# LB_BIT_o5_DCMOTOR-v02_rev1.net
KiCad netlist of a schematic drawn in EAGLE
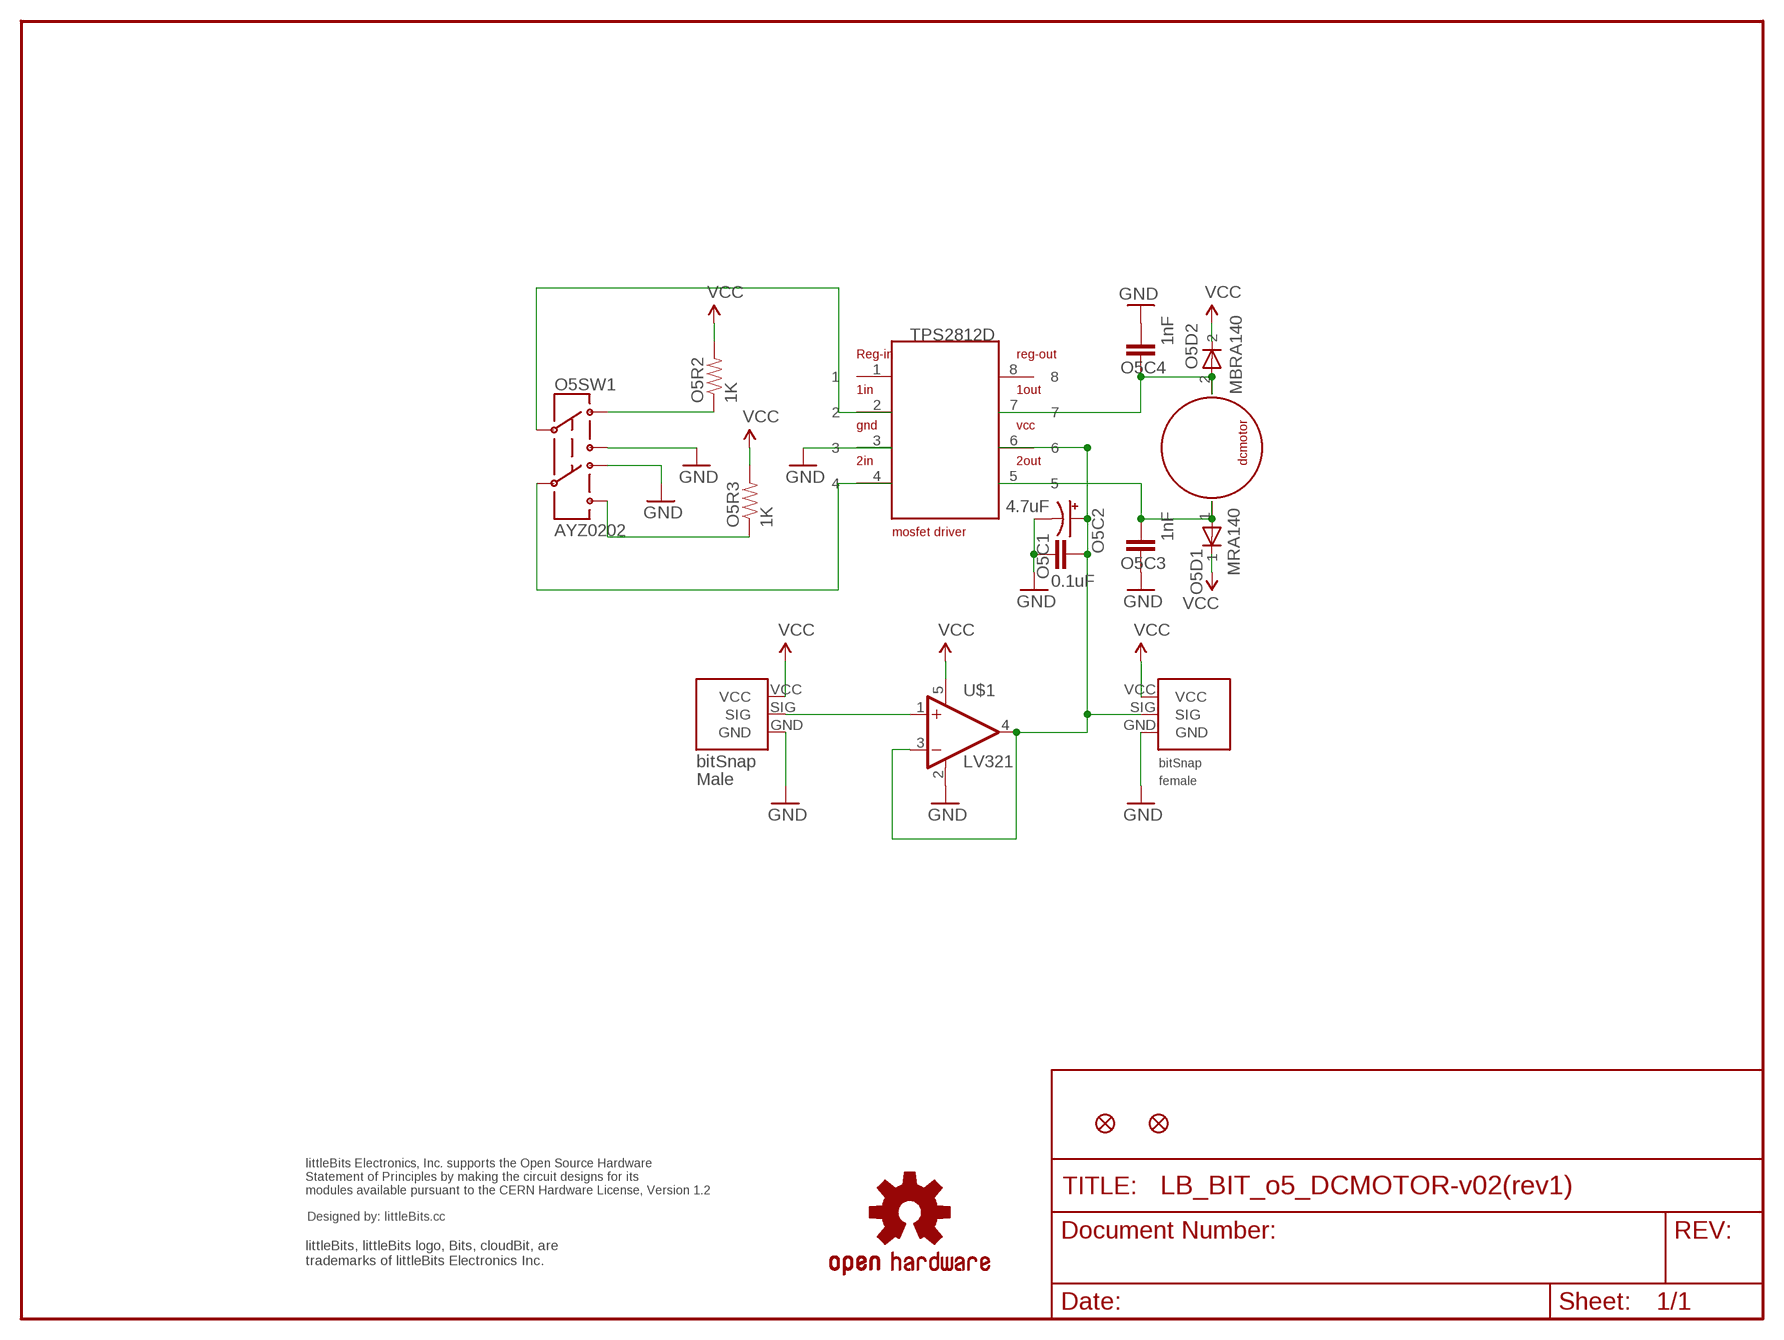
[diagram p0: schematic, sheet 1]

(export (version "E")
  (design (tool "Eeschema 10.0.6"))
  (components
    (comp (ref "JP1")
      (value "FIDUCIAL1X2")
      (footprint "eagle-import:FIDUCIAL-1X2")
      (libsource (lib "eagle-import") (part "FIDUCIAL1X2"))
    )
    (comp (ref "JP2")
      (value "FIDUCIAL1X2")
      (footprint "eagle-import:FIDUCIAL-1X2")
      (libsource (lib "eagle-import") (part "FIDUCIAL1X2"))
    )
    (comp (ref "O5BSF")
      (value "BITSNAP_FEMALE")
      (footprint "eagle-import:BITSNAP_FEMALE")
      (libsource (lib "eagle-import") (part "BITSNAP_FEMALE"))
    )
    (comp (ref "O5BSM")
      (value "BITSNAP_MALE")
      (footprint "eagle-import:BITSNAP_MALE")
      (libsource (lib "eagle-import") (part "BITSNAP_MALE"))
    )
    (comp (ref "O5C1")
      (value "0.1uF")
      (footprint "eagle-import:0603-CAP")
      (libsource (lib "eagle-import") (part "CAP0603-CAP"))
    )
    (comp (ref "O5C2")
      (value "4.7uF")
      (footprint "eagle-import:EIA3216")
      (libsource (lib "eagle-import") (part "CAP_POL1206"))
    )
    (comp (ref "O5C3")
      (value "1nF")
      (footprint "eagle-import:0603-CAP")
      (libsource (lib "eagle-import") (part "CAP0603-CAP"))
    )
    (comp (ref "O5C4")
      (value "1nF")
      (footprint "eagle-import:0603-CAP")
      (libsource (lib "eagle-import") (part "CAP0603-CAP"))
    )
    (comp (ref "O5D1")
      (value "MRA140")
      (footprint "eagle-import:SMA-DIODE")
      (libsource (lib "eagle-import") (part "DIODESMA"))
    )
    (comp (ref "O5D2")
      (value "MBRA140")
      (footprint "eagle-import:SMA-DIODE")
      (libsource (lib "eagle-import") (part "DIODESMA"))
    )
    (comp (ref "O5M1")
      (value "DCMOTOR")
      (footprint "eagle-import:MOTOR-DC")
      (libsource (lib "eagle-import") (part "DCMOTOR"))
    )
    (comp (ref "O5R2")
      (value "1K")
      (footprint "eagle-import:0603-RES")
      (libsource (lib "eagle-import") (part "RESISTOR0603-RES"))
    )
    (comp (ref "O5R3")
      (value "1K")
      (footprint "eagle-import:0603-RES")
      (libsource (lib "eagle-import") (part "RESISTOR0603-RES"))
    )
    (comp (ref "O5SW1")
      (value "AYZ0202")
      (footprint "eagle-import:AYZ0202")
      (libsource (lib "eagle-import") (part "AYZ0202"))
    )
    (comp (ref "O5U1")
      (value "TPS2812-SOIC8")
      (footprint "eagle-import:TPS2812")
      (libsource (lib "eagle-import") (part "TPS2812-SOIC8"))
    )
    (comp (ref "U$1")
      (value "LV321")
      (footprint "eagle-import:SC70-5")
      (libsource (lib "eagle-import") (part "LV321"))
    )
    (comp (ref "U$4")
      (value "OSHW-LOGOL")
      (footprint "eagle-import:OSHW-LOGO-L")
      (libsource (lib "eagle-import") (part "OSHW-LOGOL"))
    )
    (comp (ref "U$6")
      (value "OSHWCREDIT")
      (footprint "eagle-import:OSHWCREDIT")
      (libsource (lib "eagle-import") (part "OSHWCREDIT"))
    )
  )
  (nets
    (net (code "1") (name "GND") (class "Default")
      (node (ref "O5BSF") (pin "GND") (pinfunction "GND_GND") (pintype "bidirectional"))
      (node (ref "O5BSM") (pin "GND") (pinfunction "GND_GND") (pintype "bidirectional"))
      (node (ref "O5C1") (pin "1") (pinfunction "1_1") (pintype "passive"))
      (node (ref "O5C2") (pin "C") (pinfunction "-_C") (pintype "passive"))
      (node (ref "O5C3") (pin "1") (pinfunction "1_1") (pintype "passive"))
      (node (ref "O5C4") (pin "2") (pinfunction "2_2") (pintype "passive"))
      (node (ref "O5SW1") (pin "1") (pinfunction "3_1") (pintype "bidirectional"))
      (node (ref "O5SW1") (pin "6") (pinfunction "4_6") (pintype "bidirectional"))
      (node (ref "O5U1") (pin "3") (pinfunction "3_3") (pintype "bidirectional"))
      (node (ref "U$1") (pin "2") (pinfunction "V-_2") (pintype "power_in"))
    )
    (net (code "2") (name "Net-(O5C2-+)") (class "Default")
      (node (ref "O5BSF") (pin "SIG") (pinfunction "SIG_SIG") (pintype "bidirectional"))
      (node (ref "O5C1") (pin "2") (pinfunction "2_2") (pintype "passive"))
      (node (ref "O5C2") (pin "A") (pinfunction "+_A") (pintype "passive"))
      (node (ref "O5U1") (pin "6") (pinfunction "6_6") (pintype "bidirectional"))
      (node (ref "U$1") (pin "3") (pinfunction "-IN_3") (pintype "input"))
      (node (ref "U$1") (pin "4") (pinfunction "OUT_4") (pintype "output"))
    )
    (net (code "3") (name "Net-(O5C3-Pad2)") (class "Default")
      (node (ref "O5C3") (pin "2") (pinfunction "2_2") (pintype "passive"))
      (node (ref "O5D1") (pin "A") (pinfunction "A_A") (pintype "passive"))
      (node (ref "O5M1") (pin "1") (pinfunction "1_1") (pintype "bidirectional"))
      (node (ref "O5U1") (pin "5") (pinfunction "5_5") (pintype "bidirectional"))
    )
    (net (code "4") (name "Net-(O5C4-Pad1)") (class "Default")
      (node (ref "O5C4") (pin "1") (pinfunction "1_1") (pintype "passive"))
      (node (ref "O5D2") (pin "A") (pinfunction "A_A") (pintype "passive"))
      (node (ref "O5M1") (pin "2") (pinfunction "2_2") (pintype "bidirectional"))
      (node (ref "O5U1") (pin "7") (pinfunction "7_7") (pintype "bidirectional"))
    )
    (net (code "5") (name "Net-(O5SW1-1)") (class "Default")
      (node (ref "O5R2") (pin "1") (pinfunction "1_1") (pintype "passive"))
      (node (ref "O5SW1") (pin "3") (pinfunction "1_3") (pintype "bidirectional"))
    )
    (net (code "6") (name "Net-(O5SW1-6)") (class "Default")
      (node (ref "O5R3") (pin "1") (pinfunction "1_1") (pintype "passive"))
      (node (ref "O5SW1") (pin "4") (pinfunction "6_4") (pintype "bidirectional"))
    )
    (net (code "7") (name "Net-(O5SW1-Pad2)") (class "Default")
      (node (ref "O5SW1") (pin "2") (pinfunction "2_2") (pintype "bidirectional"))
      (node (ref "O5U1") (pin "2") (pinfunction "2_2") (pintype "bidirectional"))
    )
    (net (code "8") (name "Net-(O5SW1-Pad5)") (class "Default")
      (node (ref "O5SW1") (pin "5") (pinfunction "5_5") (pintype "bidirectional"))
      (node (ref "O5U1") (pin "4") (pinfunction "4_4") (pintype "bidirectional"))
    )
    (net (code "9") (name "Net-(U$1-+IN)") (class "Default")
      (node (ref "O5BSM") (pin "SIG") (pinfunction "SIG_SIG") (pintype "bidirectional"))
      (node (ref "U$1") (pin "1") (pinfunction "+IN_1") (pintype "input"))
    )
    (net (code "10") (name "VCC") (class "Default")
      (node (ref "O5BSF") (pin "VCC") (pinfunction "VCC_VCC") (pintype "bidirectional"))
      (node (ref "O5BSM") (pin "VCC") (pinfunction "VCC_VCC") (pintype "bidirectional"))
      (node (ref "O5D1") (pin "C") (pinfunction "C_C") (pintype "passive"))
      (node (ref "O5D2") (pin "C") (pinfunction "C_C") (pintype "passive"))
      (node (ref "O5R2") (pin "2") (pinfunction "2_2") (pintype "passive"))
      (node (ref "O5R3") (pin "2") (pinfunction "2_2") (pintype "passive"))
      (node (ref "U$1") (pin "5") (pinfunction "V+_5") (pintype "power_in"))
    )
    (net (code "11") (name "unconnected-(O5U1-Pad1)") (class "Default")
      (node (ref "O5U1") (pin "1") (pinfunction "1_1") (pintype "bidirectional"))
    )
    (net (code "12") (name "unconnected-(O5U1-Pad8)") (class "Default")
      (node (ref "O5U1") (pin "8") (pinfunction "8_8") (pintype "bidirectional"))
    )
  )
)
